# mainboard_interface_v1_6.net
KiCad netlist of a schematic drawn in Altium Designer
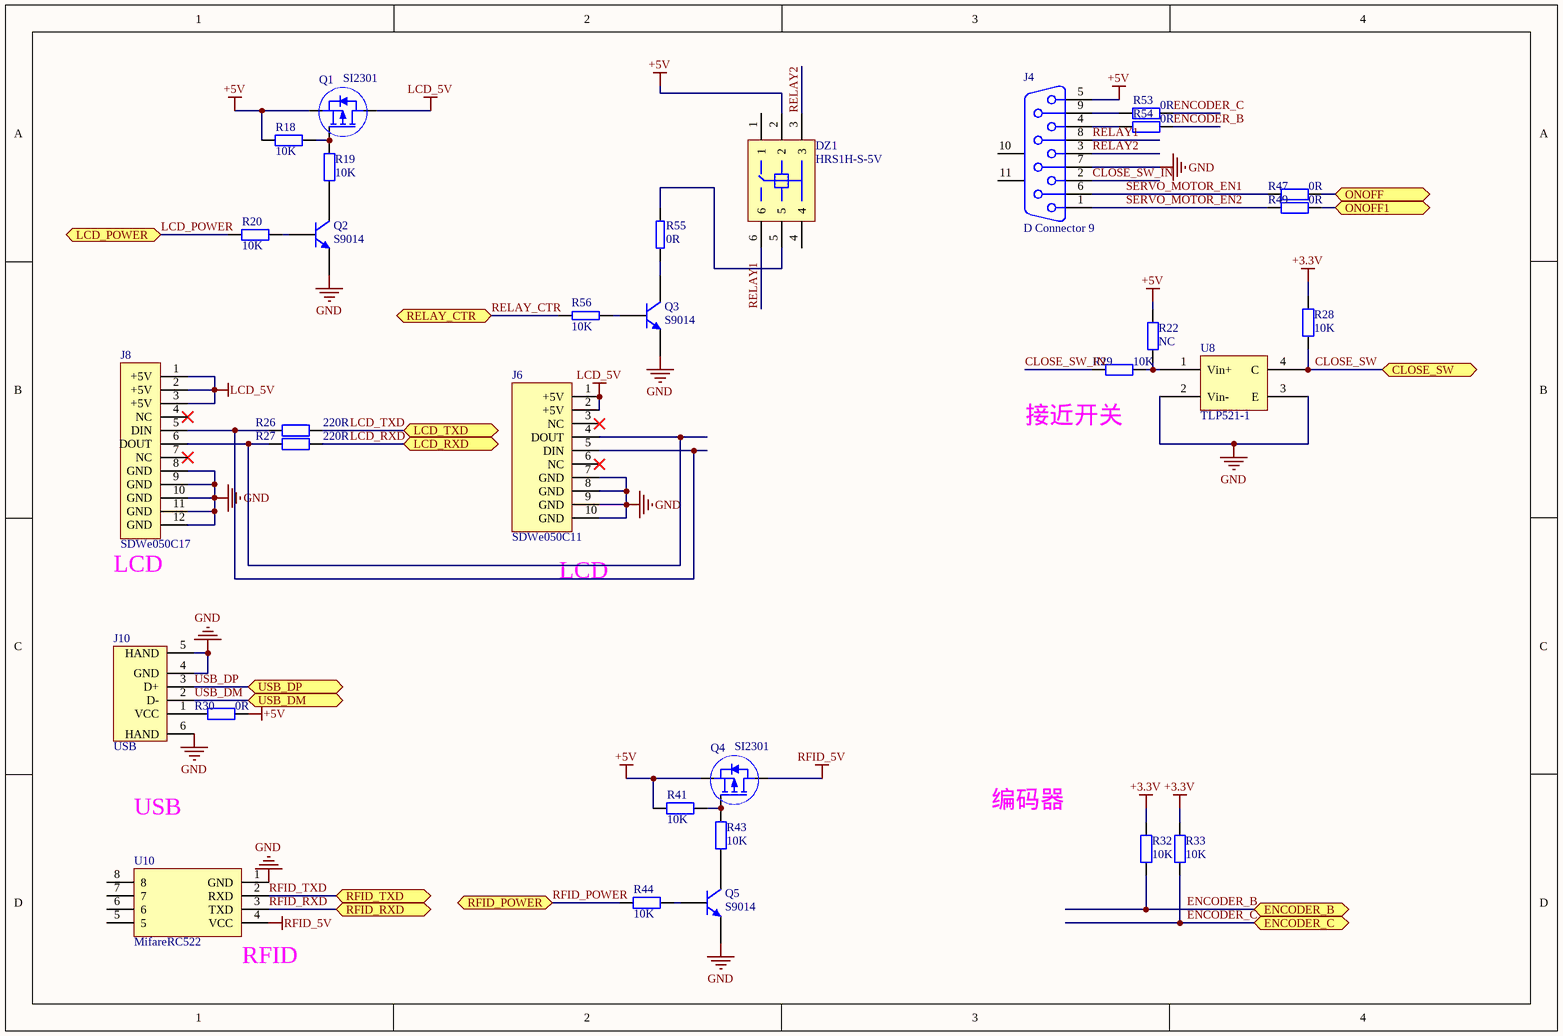
[diagram p0: mainboard_interface.v1.6.SchDoc]

(export (version "E")
  (design (tool "Eeschema 10.0.6"))
  (components
    (comp (ref "DZ1")
      (value "HRS1H-S-5V")
      (footprint "HRS1H-S-DC5")
      (libsource (lib "Componet") (part "HRS1H-S-5V"))
    )
    (comp (ref "J4")
      (value "D Connector 9")
      (footprint "DSUB1.385-2H9")
      (description "Receptacle Assembly, 9 Position, Right Angle")
      (fields (field (name "PUBLISHER") "Altium Limited"))
      (libsource (lib "Miscellaneous Connectors") (part "D Connector 9"))
    )
    (comp (ref "J6")
      (value "SDWe050C11")
      (footprint "8PIN_2.0SMD")
      (libsource (lib "Componet") (part "SDWe043T04"))
    )
    (comp (ref "J8")
      (value "SDWe050C17")
      (footprint "FCC1.0-10")
      (libsource (lib "Connector") (part "SH-12"))
    )
    (comp (ref "J10") (value "USB") (footprint "USB_FEMALE_A") (libsource (lib "Connector") (part "USB")))
    (comp (ref "Q1") (value "SI2301") (footprint "MOS-N_SOT-23") (libsource (lib "*") (part "MOS-P_SOT-23")))
    (comp (ref "Q2") (value "S9014") (footprint "901X_SOT-23") (libsource (lib "Componet") (part "NPN")))
    (comp (ref "Q3") (value "S9014") (footprint "901X_SOT-23") (libsource (lib "Componet") (part "NPN")))
    (comp (ref "Q4") (value "SI2301") (footprint "MOS-N_SOT-23") (libsource (lib "*") (part "MOS-P_SOT-23")))
    (comp (ref "Q5") (value "S9014") (footprint "901X_SOT-23") (libsource (lib "Componet") (part "NPN")))
    (comp (ref "R18")
      (value "10K")
      (footprint "0805")
      (description "Resistor")
      (fields (field (name "PUBLISHER") "Altium Limited"))
      (libsource (lib "TIAN's Schlib") (part "Res2"))
    )
    (comp (ref "R19")
      (value "10K")
      (footprint "0805")
      (description "Resistor")
      (fields (field (name "PUBLISHER") "Altium Limited"))
      (libsource (lib "") (part "Res2_3"))
    )
    (comp (ref "R20")
      (value "10K")
      (footprint "0805")
      (description "Resistor")
      (fields (field (name "PUBLISHER") "Altium Limited"))
      (libsource (lib "TIAN's Schlib") (part "Res2"))
    )
    (comp (ref "R22")
      (value "NC")
      (footprint "0805")
      (description "Resistor")
      (fields (field (name "PUBLISHER") "Altium Limited"))
      (libsource (lib "") (part "Res2_2"))
    )
    (comp (ref "R26")
      (value "220R")
      (footprint "0805")
      (description "Resistor")
      (fields (field (name "PUBLISHER") "Altium Limited"))
      (libsource (lib "TIAN's Schlib") (part "Res2"))
    )
    (comp (ref "R27")
      (value "220R")
      (footprint "0805")
      (description "Resistor")
      (fields (field (name "PUBLISHER") "Altium Limited"))
      (libsource (lib "TIAN's Schlib") (part "Res2"))
    )
    (comp (ref "R28")
      (value "10K")
      (footprint "0805")
      (description "Resistor")
      (fields (field (name "PUBLISHER") "Altium Limited"))
      (libsource (lib "") (part "Res2_2"))
    )
    (comp (ref "R29")
      (value "10K")
      (footprint "0805")
      (description "Resistor")
      (fields (field (name "PUBLISHER") "Altium Limited"))
      (libsource (lib "") (part "Res2_1"))
    )
    (comp (ref "R30")
      (value "0R")
      (footprint "0805")
      (description "Resistor")
      (fields (field (name "PUBLISHER") "Altium Limited"))
      (libsource (lib "") (part "Res2_1"))
    )
    (comp (ref "R32")
      (value "10K")
      (footprint "0805")
      (description "Resistor")
      (fields (field (name "PUBLISHER") "Altium Limited"))
      (libsource (lib "") (part "Res2_2"))
    )
    (comp (ref "R33")
      (value "10K")
      (footprint "0805")
      (description "Resistor")
      (fields (field (name "PUBLISHER") "Altium Limited"))
      (libsource (lib "") (part "Res2_2"))
    )
    (comp (ref "R41")
      (value "10K")
      (footprint "0805")
      (description "Resistor")
      (fields (field (name "PUBLISHER") "Altium Limited"))
      (libsource (lib "TIAN's Schlib") (part "Res2"))
    )
    (comp (ref "R43")
      (value "10K")
      (footprint "0805")
      (description "Resistor")
      (fields (field (name "PUBLISHER") "Altium Limited"))
      (libsource (lib "") (part "Res2_3"))
    )
    (comp (ref "R44")
      (value "10K")
      (footprint "0805")
      (description "Resistor")
      (fields (field (name "PUBLISHER") "Altium Limited"))
      (libsource (lib "TIAN's Schlib") (part "Res2"))
    )
    (comp (ref "R47")
      (value "0R")
      (footprint "0805")
      (description "Resistor")
      (fields (field (name "PUBLISHER") "Altium Limited"))
      (libsource (lib "") (part "Res2_1"))
    )
    (comp (ref "R49")
      (value "0R")
      (footprint "0805")
      (description "Resistor")
      (fields (field (name "PUBLISHER") "Altium Limited"))
      (libsource (lib "") (part "Res2_1"))
    )
    (comp (ref "R53")
      (value "0R")
      (footprint "0805")
      (description "Resistor")
      (fields (field (name "PUBLISHER") "Altium Limited"))
      (libsource (lib "TIAN's Schlib") (part "Res2"))
    )
    (comp (ref "R54")
      (value "0R")
      (footprint "0805")
      (description "Resistor")
      (fields (field (name "PUBLISHER") "Altium Limited"))
      (libsource (lib "TIAN's Schlib") (part "Res2"))
    )
    (comp (ref "R55")
      (value "0R")
      (footprint "0805")
      (description "电阻")
      (libsource (lib "Component") (part "RES"))
    )
    (comp (ref "R56")
      (value "10K")
      (footprint "0805")
      (description "电阻")
      (libsource (lib "Component") (part "RES"))
    )
    (comp (ref "U8") (value "TLP521-1") (footprint "TLP521-1") (libsource (lib "Chip") (part "TLP521-1")))
    (comp (ref "U10")
      (value "MifareRC522")
      (footprint "MifareRC522")
      (libsource (lib "Componet") (part "MifareRC522"))
    )
  )
  (nets
    (net (code "1") (name "+3.3V") (class "Default")
      (node (ref "R28") (pin "1") (pinfunction "1_1") (pintype "passive"))
      (node (ref "R32") (pin "1") (pinfunction "1_1") (pintype "passive"))
      (node (ref "R33") (pin "1") (pinfunction "1_1") (pintype "passive"))
    )
    (net (code "2") (name "+5V") (class "Default")
      (node (ref "DZ1") (pin "2") (pinfunction "2_2") (pintype "passive"))
      (node (ref "J4") (pin "5") (pinfunction "5_5") (pintype "passive"))
      (node (ref "Q1") (pin "S") (pinfunction "S_S") (pintype "passive"))
      (node (ref "Q4") (pin "S") (pinfunction "S_S") (pintype "passive"))
      (node (ref "R18") (pin "1") (pinfunction "1_1") (pintype "passive"))
      (node (ref "R22") (pin "1") (pinfunction "1_1") (pintype "passive"))
      (node (ref "R30") (pin "1") (pinfunction "1_1") (pintype "passive"))
      (node (ref "R41") (pin "1") (pinfunction "1_1") (pintype "passive"))
    )
    (net (code "3") (name "/CLOSE_SW") (class "Default")
      (node (ref "R28") (pin "2") (pinfunction "2_2") (pintype "passive"))
      (node (ref "U8") (pin "4") (pinfunction "C_4") (pintype "passive"))
    )
    (net (code "4") (name "/CLOSE_SW_IN") (class "Default")
      (node (ref "J4") (pin "2") (pinfunction "2_2") (pintype "passive"))
      (node (ref "R29") (pin "2") (pinfunction "2_2") (pintype "passive"))
    )
    (net (code "5") (name "/ENCODER_B") (class "Default")
      (node (ref "R32") (pin "2") (pinfunction "2_2") (pintype "passive"))
      (node (ref "R54") (pin "2") (pinfunction "2_2") (pintype "passive"))
    )
    (net (code "6") (name "/ENCODER_C") (class "Default")
      (node (ref "R33") (pin "2") (pinfunction "2_2") (pintype "passive"))
      (node (ref "R53") (pin "2") (pinfunction "2_2") (pintype "passive"))
    )
    (net (code "7") (name "/LCD_POWER") (class "Default")
      (node (ref "R20") (pin "1") (pinfunction "1_1") (pintype "passive"))
    )
    (net (code "8") (name "/LCD_RXD") (class "Default")
      (node (ref "R27") (pin "2") (pinfunction "2_2") (pintype "passive"))
    )
    (net (code "9") (name "/LCD_TXD") (class "Default")
      (node (ref "R26") (pin "2") (pinfunction "2_2") (pintype "passive"))
    )
    (net (code "10") (name "/ONOFF") (class "Default")
      (node (ref "R47") (pin "1") (pinfunction "1_1") (pintype "passive"))
    )
    (net (code "11") (name "/ONOFF1") (class "Default")
      (node (ref "R49") (pin "1") (pinfunction "1_1") (pintype "passive"))
    )
    (net (code "12") (name "/RELAY1") (class "Default")
      (node (ref "DZ1") (pin "6") (pinfunction "6_6") (pintype "passive"))
      (node (ref "J4") (pin "8") (pinfunction "8_8") (pintype "passive"))
    )
    (net (code "13") (name "/RELAY2") (class "Default")
      (node (ref "DZ1") (pin "3") (pinfunction "3_3") (pintype "passive"))
      (node (ref "J4") (pin "3") (pinfunction "3_3") (pintype "passive"))
    )
    (net (code "14") (name "/RELAY_CTR") (class "Default")
      (node (ref "R56") (pin "2") (pinfunction "2_2") (pintype "passive"))
    )
    (net (code "15") (name "/RFID_POWER") (class "Default")
      (node (ref "R44") (pin "1") (pinfunction "1_1") (pintype "passive"))
    )
    (net (code "16") (name "/RFID_RXD") (class "Default")
      (node (ref "U10") (pin "3") (pinfunction "TXD_3") (pintype "passive"))
    )
    (net (code "17") (name "/RFID_TXD") (class "Default")
      (node (ref "U10") (pin "2") (pinfunction "RXD_2") (pintype "passive"))
    )
    (net (code "18") (name "/SERVO_MOTOR_EN1") (class "Default")
      (node (ref "J4") (pin "6") (pinfunction "6_6") (pintype "passive"))
      (node (ref "R47") (pin "2") (pinfunction "2_2") (pintype "passive"))
    )
    (net (code "19") (name "/SERVO_MOTOR_EN2") (class "Default")
      (node (ref "J4") (pin "1") (pinfunction "1_1") (pintype "passive"))
      (node (ref "R49") (pin "2") (pinfunction "2_2") (pintype "passive"))
    )
    (net (code "20") (name "/USB_DM") (class "Default")
      (node (ref "J10") (pin "2") (pinfunction "D-_2") (pintype "passive"))
    )
    (net (code "21") (name "/USB_DP") (class "Default")
      (node (ref "J10") (pin "3") (pinfunction "D+_3") (pintype "passive"))
    )
    (net (code "22") (name "GND") (class "Default")
      (node (ref "J10") (pin "4") (pinfunction "GND_4") (pintype "passive"))
      (node (ref "J10") (pin "5") (pinfunction "HAND_5") (pintype "passive"))
      (node (ref "J10") (pin "6") (pinfunction "HAND_6") (pintype "passive"))
      (node (ref "J4") (pin "7") (pinfunction "7_7") (pintype "passive"))
      (node (ref "J6") (pin "10") (pinfunction "GND_10") (pintype "passive"))
      (node (ref "J6") (pin "7") (pinfunction "GND_7") (pintype "passive"))
      (node (ref "J6") (pin "8") (pinfunction "GND_8") (pintype "passive"))
      (node (ref "J6") (pin "9") (pinfunction "GND_9") (pintype "passive"))
      (node (ref "J8") (pin "10") (pinfunction "GND_10") (pintype "passive"))
      (node (ref "J8") (pin "11") (pinfunction "GND_11") (pintype "passive"))
      (node (ref "J8") (pin "12") (pinfunction "GND_12") (pintype "passive"))
      (node (ref "J8") (pin "8") (pinfunction "GND_8") (pintype "passive"))
      (node (ref "J8") (pin "9") (pinfunction "GND_9") (pintype "passive"))
      (node (ref "Q2") (pin "3") (pinfunction "E_3") (pintype "passive"))
      (node (ref "Q3") (pin "3") (pinfunction "E_3") (pintype "passive"))
      (node (ref "Q5") (pin "3") (pinfunction "E_3") (pintype "passive"))
      (node (ref "U10") (pin "1") (pinfunction "GND_1") (pintype "passive"))
      (node (ref "U8") (pin "2") (pinfunction "Vin-_2") (pintype "passive"))
      (node (ref "U8") (pin "3") (pinfunction "E_3") (pintype "passive"))
    )
    (net (code "23") (name "LCD_5V") (class "Default")
      (node (ref "J6") (pin "1") (pinfunction "+5V_1") (pintype "passive"))
      (node (ref "J6") (pin "2") (pinfunction "+5V_2") (pintype "passive"))
      (node (ref "J8") (pin "1") (pinfunction "+5V_1") (pintype "passive"))
      (node (ref "J8") (pin "2") (pinfunction "+5V_2") (pintype "passive"))
      (node (ref "J8") (pin "3") (pinfunction "+5V_3") (pintype "passive"))
      (node (ref "Q1") (pin "D") (pinfunction "D_D") (pintype "passive"))
    )
    (net (code "24") (name "Net-(DZ1-Pad5)") (class "Default")
      (node (ref "DZ1") (pin "5") (pinfunction "5_5") (pintype "passive"))
      (node (ref "R55") (pin "2") (pinfunction "2_2") (pintype "passive"))
    )
    (net (code "25") (name "Net-(J4-Pad4)") (class "Default")
      (node (ref "J4") (pin "4") (pinfunction "4_4") (pintype "passive"))
      (node (ref "R54") (pin "1") (pinfunction "1_1") (pintype "passive"))
    )
    (net (code "26") (name "Net-(J4-Pad9)") (class "Default")
      (node (ref "J4") (pin "9") (pinfunction "9_9") (pintype "passive"))
      (node (ref "R53") (pin "1") (pinfunction "1_1") (pintype "passive"))
    )
    (net (code "27") (name "Net-(J6-DIN)") (class "Default")
      (node (ref "J6") (pin "5") (pinfunction "DIN_5") (pintype "passive"))
      (node (ref "J8") (pin "5") (pinfunction "DIN_5") (pintype "passive"))
      (node (ref "R26") (pin "1") (pinfunction "1_1") (pintype "passive"))
    )
    (net (code "28") (name "Net-(J6-DOUT)") (class "Default")
      (node (ref "J6") (pin "4") (pinfunction "DOUT_4") (pintype "passive"))
      (node (ref "J8") (pin "6") (pinfunction "DOUT_6") (pintype "passive"))
      (node (ref "R27") (pin "1") (pinfunction "1_1") (pintype "passive"))
    )
    (net (code "29") (name "Net-(J10-VCC)") (class "Default")
      (node (ref "J10") (pin "1") (pinfunction "VCC_1") (pintype "passive"))
      (node (ref "R30") (pin "2") (pinfunction "2_2") (pintype "passive"))
    )
    (net (code "30") (name "Net-(Q1-PadG)") (class "Default")
      (node (ref "Q1") (pin "G") (pinfunction "G_G") (pintype "passive"))
      (node (ref "R18") (pin "2") (pinfunction "2_2") (pintype "passive"))
      (node (ref "R19") (pin "2") (pinfunction "2_2") (pintype "passive"))
    )
    (net (code "31") (name "Net-(Q2-B)") (class "Default")
      (node (ref "Q2") (pin "2") (pinfunction "B_2") (pintype "passive"))
      (node (ref "R20") (pin "2") (pinfunction "2_2") (pintype "passive"))
    )
    (net (code "32") (name "Net-(Q2-C)") (class "Default")
      (node (ref "Q2") (pin "1") (pinfunction "C_1") (pintype "passive"))
      (node (ref "R19") (pin "1") (pinfunction "1_1") (pintype "passive"))
    )
    (net (code "33") (name "Net-(Q3-B)") (class "Default")
      (node (ref "Q3") (pin "2") (pinfunction "B_2") (pintype "passive"))
      (node (ref "R56") (pin "1") (pinfunction "1_1") (pintype "passive"))
    )
    (net (code "34") (name "Net-(Q3-C)") (class "Default")
      (node (ref "Q3") (pin "1") (pinfunction "C_1") (pintype "passive"))
      (node (ref "R55") (pin "1") (pinfunction "1_1") (pintype "passive"))
    )
    (net (code "35") (name "Net-(Q4-PadG)") (class "Default")
      (node (ref "Q4") (pin "G") (pinfunction "G_G") (pintype "passive"))
      (node (ref "R41") (pin "2") (pinfunction "2_2") (pintype "passive"))
      (node (ref "R43") (pin "2") (pinfunction "2_2") (pintype "passive"))
    )
    (net (code "36") (name "Net-(Q5-B)") (class "Default")
      (node (ref "Q5") (pin "2") (pinfunction "B_2") (pintype "passive"))
      (node (ref "R44") (pin "2") (pinfunction "2_2") (pintype "passive"))
    )
    (net (code "37") (name "Net-(Q5-C)") (class "Default")
      (node (ref "Q5") (pin "1") (pinfunction "C_1") (pintype "passive"))
      (node (ref "R43") (pin "1") (pinfunction "1_1") (pintype "passive"))
    )
    (net (code "38") (name "Net-(U8-Vin+)") (class "Default")
      (node (ref "R22") (pin "2") (pinfunction "2_2") (pintype "passive"))
      (node (ref "R29") (pin "1") (pinfunction "1_1") (pintype "passive"))
      (node (ref "U8") (pin "1") (pinfunction "Vin+_1") (pintype "passive"))
    )
    (net (code "39") (name "RFID_5V") (class "Default")
      (node (ref "Q4") (pin "D") (pinfunction "D_D") (pintype "passive"))
      (node (ref "U10") (pin "4") (pinfunction "VCC_4") (pintype "passive"))
    )
    (net (code "40") (name "unconnected-(DZ1-Pad1)") (class "Default")
      (node (ref "DZ1") (pin "1") (pinfunction "1_1") (pintype "passive"))
    )
    (net (code "41") (name "unconnected-(DZ1-Pad4)") (class "Default")
      (node (ref "DZ1") (pin "4") (pinfunction "4_4") (pintype "passive"))
    )
    (net (code "42") (name "unconnected-(J4-MH1-Pad10)") (class "Default")
      (node (ref "J4") (pin "10") (pinfunction "MH1_10") (pintype "passive"))
    )
    (net (code "43") (name "unconnected-(J4-MH2-Pad11)") (class "Default")
      (node (ref "J4") (pin "11") (pinfunction "MH2_11") (pintype "passive"))
    )
    (net (code "44") (name "unconnected-(J6-NC-Pad3)") (class "Default")
      (node (ref "J6") (pin "3") (pinfunction "NC_3") (pintype "passive+no_connect"))
    )
    (net (code "45") (name "unconnected-(J6-NC-Pad6)") (class "Default")
      (node (ref "J6") (pin "6") (pinfunction "NC_6") (pintype "passive+no_connect"))
    )
    (net (code "46") (name "unconnected-(J8-NC-Pad4)") (class "Default")
      (node (ref "J8") (pin "4") (pinfunction "NC_4") (pintype "passive+no_connect"))
    )
    (net (code "47") (name "unconnected-(J8-NC-Pad7)") (class "Default")
      (node (ref "J8") (pin "7") (pinfunction "NC_7") (pintype "passive+no_connect"))
    )
    (net (code "48") (name "unconnected-(U10-Pad5)") (class "Default")
      (node (ref "U10") (pin "5") (pinfunction "5_5") (pintype "passive"))
    )
    (net (code "49") (name "unconnected-(U10-Pad6)") (class "Default")
      (node (ref "U10") (pin "6") (pinfunction "6_6") (pintype "passive"))
    )
    (net (code "50") (name "unconnected-(U10-Pad7)") (class "Default")
      (node (ref "U10") (pin "7") (pinfunction "7_7") (pintype "passive"))
    )
    (net (code "51") (name "unconnected-(U10-Pad8)") (class "Default")
      (node (ref "U10") (pin "8") (pinfunction "8_8") (pintype "passive"))
    )
  )
)
